# LCL_CAN.net
KiCad netlist of a schematic drawn in Altium Designer
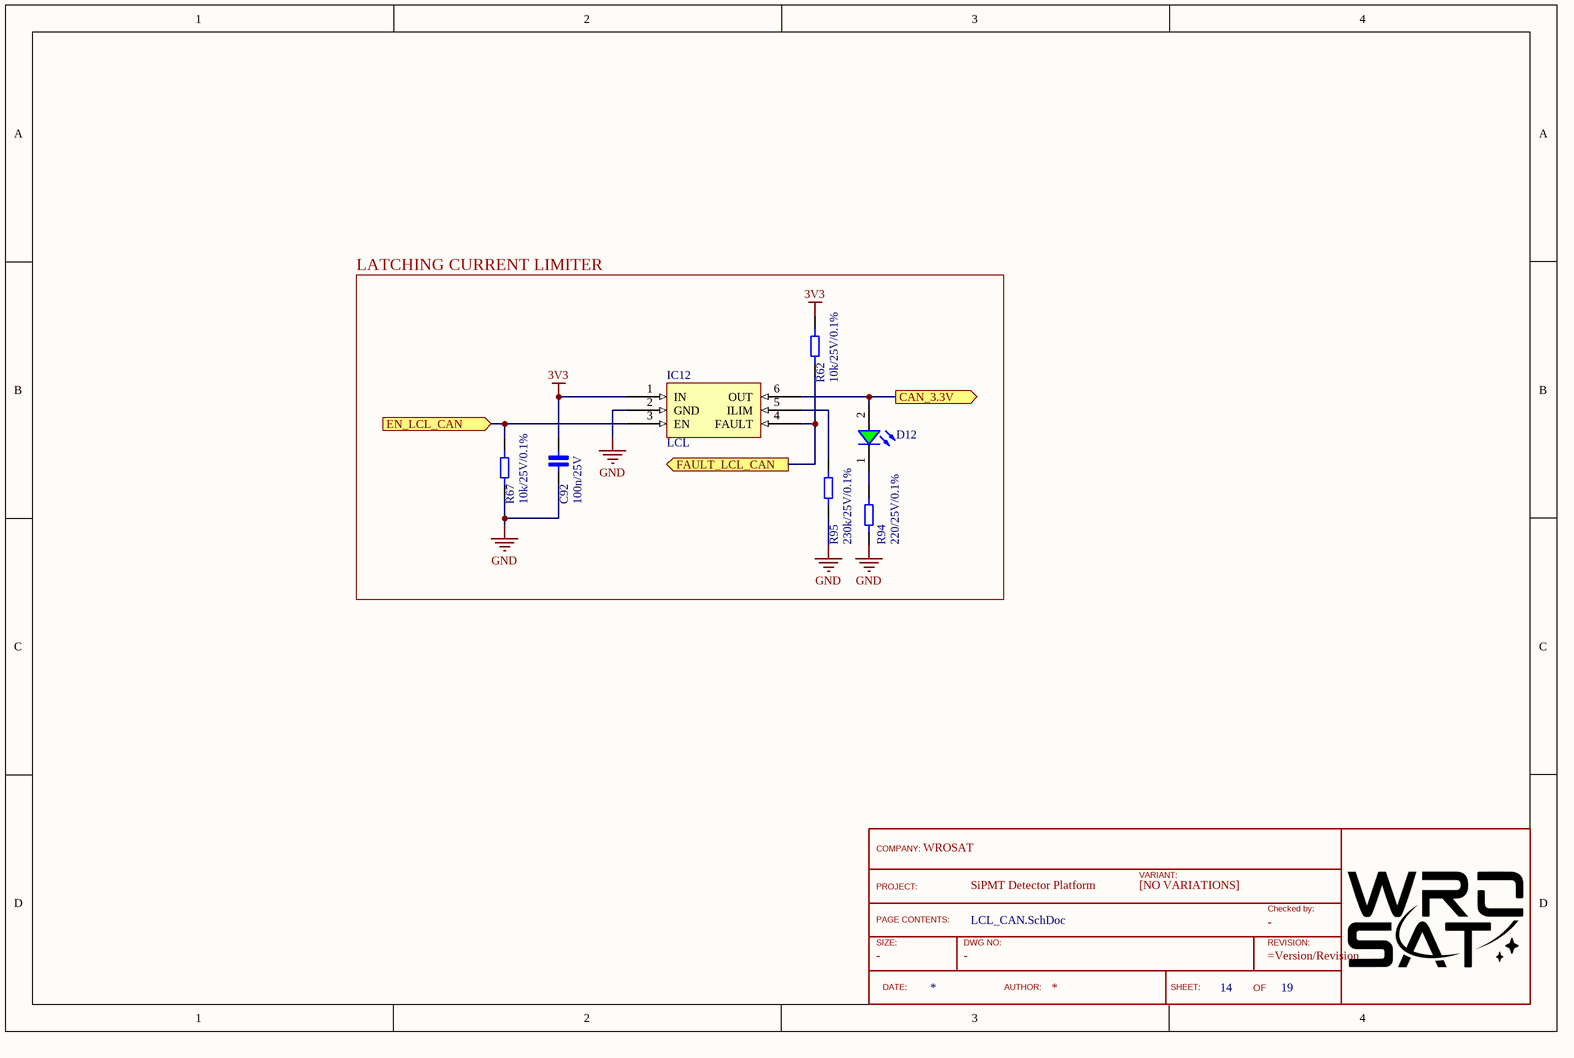
[diagram p0: LCL_CAN.SchDoc]

(export (version "E")
  (design (tool "Eeschema 10.0.6"))
  (components
    (comp (ref "C92")
      (value "100n/25V")
      (footprint "Cap_0402")
      (description "Ceramic Capacitor 100n / 0402 / 25V / ±5%, Wurth Elektronik MLCC")
      (libsource (lib "Cubesat_lib") (part "Cap_0402_100n"))
    )
    (comp (ref "D12")
      (value "Green, 3.2V")
      (footprint "WL-SMCW_0603_H=0.7mm")
      (description "WL-SMCW SMT Mono-color Chip LED Waterclear, size 0603, Green, 3.2V, 140deg")
      (fields (field (name "PART NUMBER") "150060GS75000") (field (name "PUBLISHER") "Wurth Elektronik"))
      (libsource (lib "LEDS") (part "150060GS75000"))
    )
    (comp (ref "IC12")
      (value "LCL")
      (footprint "SOT-23-6")
      (description "Latch-off Current Limiter")
      (libsource (lib "Cubesat_lib") (part "TPS2553"))
    )
    (comp (ref "R62")
      (value "10k/25V/0.1%")
      (footprint "RES_0402")
      (description "Vishay, thin film resistor 10k/25V/0.1%")
      (libsource (lib "Cubesat_lib") (part "Res_0402_10k"))
    )
    (comp (ref "R67")
      (value "10k/25V/0.1%")
      (footprint "RES_0402")
      (description "Vishay, thin film resistor 10k/25V/0.1%")
      (libsource (lib "Cubesat_lib") (part "Res_0402_10k"))
    )
    (comp (ref "R94")
      (value "220/25V/0.1%")
      (footprint "RES_0402")
      (description "Vishay, thin film resistor 1/25V/0.1%")
      (libsource (lib "Cubesat_lib") (part "Res_0402_1"))
    )
    (comp (ref "R95")
      (value "230k/25V/0.1%")
      (footprint "RES_0402")
      (description "Vishay, thin film resistor 230k/25V/0.1%")
      (libsource (lib "Cubesat_lib") (part "Res_0402_230k"))
    )
  )
  (nets
    (net (code "1") (name "/CAN_3.3V") (class "Default")
      (node (ref "D12") (pin "2") (pinfunction "A_2") (pintype "passive"))
      (node (ref "IC12") (pin "6") (pinfunction "OUT_6") (pintype "input"))
    )
    (net (code "2") (name "/EN_LCL_CAN") (class "Default")
      (node (ref "IC12") (pin "3") (pinfunction "EN_3") (pintype "input"))
      (node (ref "R67") (pin "2") (pinfunction "2_2") (pintype "passive"))
    )
    (net (code "3") (name "/FAULT_LCL_CAN") (class "Default")
      (node (ref "IC12") (pin "4") (pinfunction "FAULT_4") (pintype "input"))
      (node (ref "R62") (pin "1") (pinfunction "1_1") (pintype "passive"))
    )
    (net (code "4") (name "3V3") (class "Default")
      (node (ref "C92") (pin "2") (pinfunction "2_2") (pintype "passive"))
      (node (ref "IC12") (pin "1") (pinfunction "IN_1") (pintype "input"))
      (node (ref "R62") (pin "2") (pinfunction "2_2") (pintype "passive"))
    )
    (net (code "5") (name "GND") (class "Default")
      (node (ref "C92") (pin "1") (pinfunction "1_1") (pintype "passive"))
      (node (ref "IC12") (pin "2") (pinfunction "GND_2") (pintype "input"))
      (node (ref "R67") (pin "1") (pinfunction "1_1") (pintype "passive"))
      (node (ref "R94") (pin "1") (pinfunction "1_1") (pintype "passive"))
      (node (ref "R95") (pin "1") (pinfunction "1_1") (pintype "passive"))
    )
    (net (code "6") (name "Net-(D12-K)") (class "Default")
      (node (ref "D12") (pin "1") (pinfunction "K_1") (pintype "passive"))
      (node (ref "R94") (pin "2") (pinfunction "2_2") (pintype "passive"))
    )
    (net (code "7") (name "Net-(IC12-ILIM)") (class "Default")
      (node (ref "IC12") (pin "5") (pinfunction "ILIM_5") (pintype "input"))
      (node (ref "R95") (pin "2") (pinfunction "2_2") (pintype "passive"))
    )
  )
)
